# MegaShield.net
KiCad netlist of a schematic drawn in EAGLE
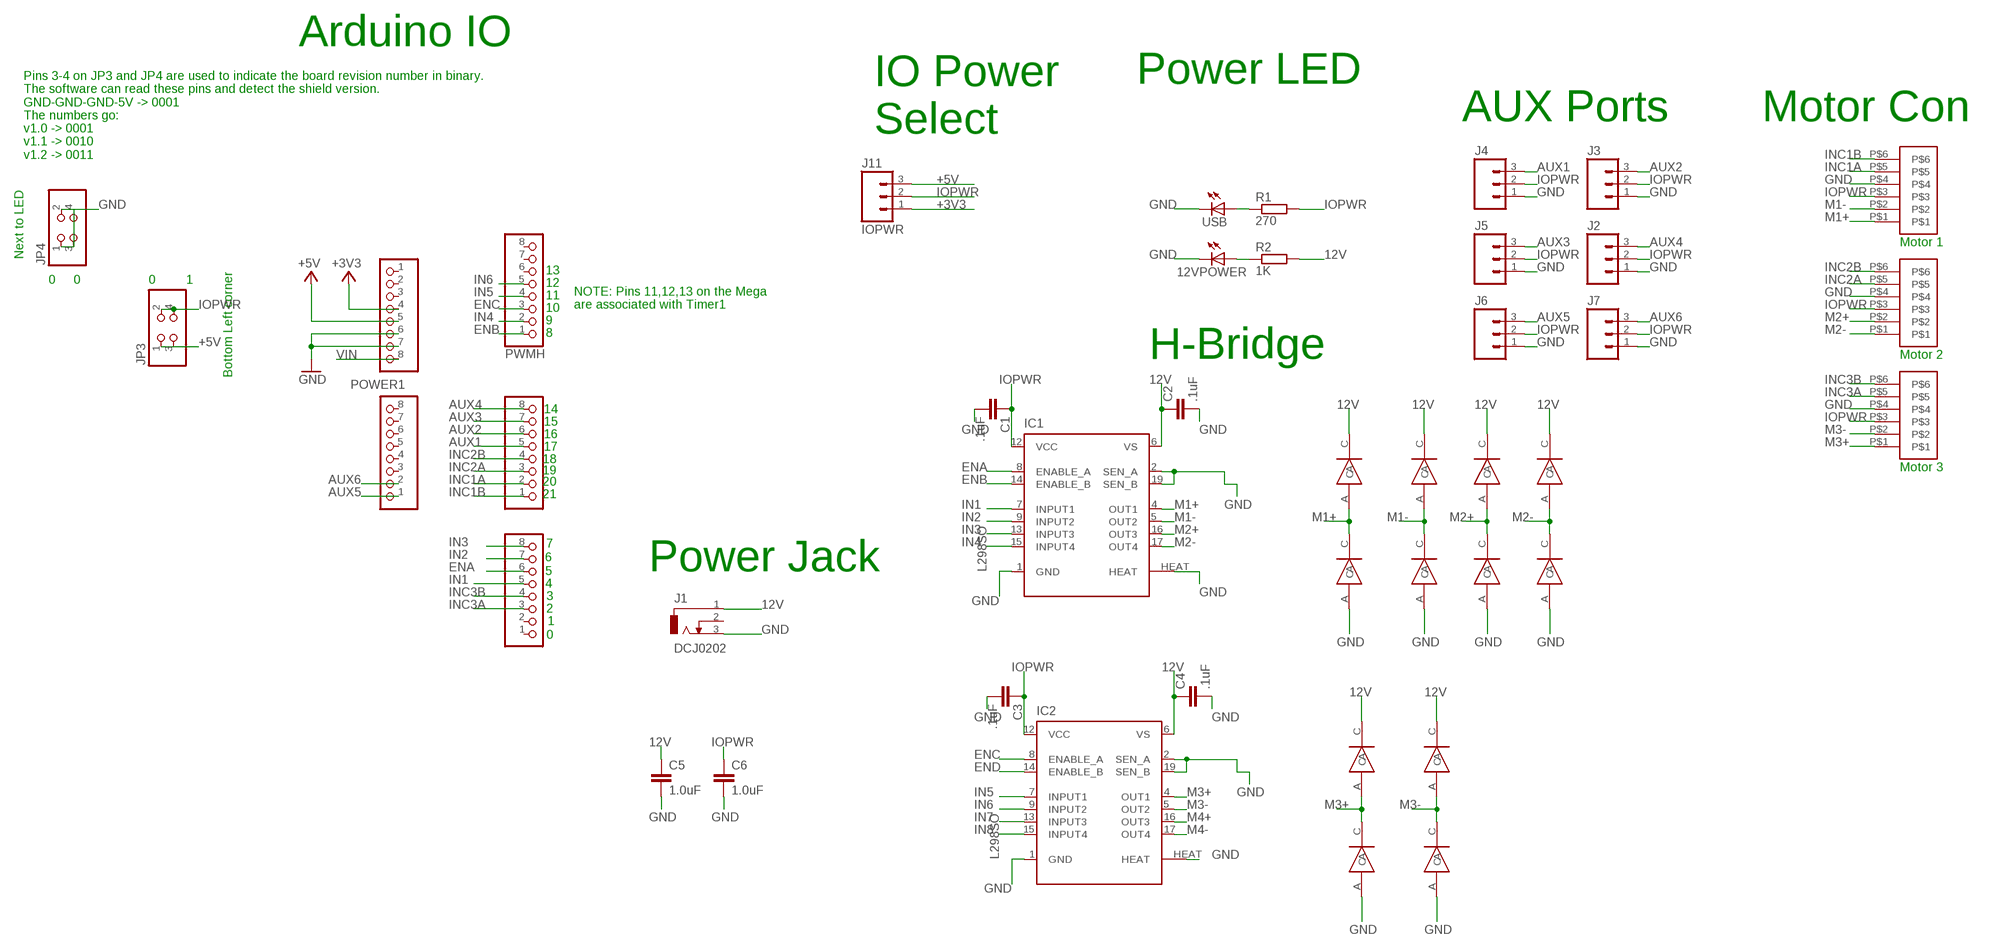
[diagram p0: schematic, sheet 1]

(export (version "E")
  (design (tool "Eeschema 10.0.6"))
  (components
    (comp (ref "12VPOWER")
      (value "LED_E")
      (footprint "eagle-import:LED_1206")
      (libsource (lib "eagle-import") (part "LED_E"))
    )
    (comp (ref "C1")
      (value ".1uF")
      (footprint "eagle-import:C0805")
      (libsource (lib "eagle-import") (part "C"))
    )
    (comp (ref "C2")
      (value ".1uF")
      (footprint "eagle-import:C0805")
      (libsource (lib "eagle-import") (part "C"))
    )
    (comp (ref "C3")
      (value ".1uF")
      (footprint "eagle-import:C0805")
      (libsource (lib "eagle-import") (part "C"))
    )
    (comp (ref "C4")
      (value ".1uF")
      (footprint "eagle-import:C0805")
      (libsource (lib "eagle-import") (part "C"))
    )
    (comp (ref "C5")
      (value "1.0uF")
      (footprint "eagle-import:0805-CAP")
      (libsource (lib "eagle-import") (part "1.0UF-25V-+80/-20(0805){dblquote}"))
    )
    (comp (ref "C6")
      (value "1.0uF")
      (footprint "eagle-import:0805-CAP")
      (libsource (lib "eagle-import") (part "1.0UF-25V-+80/-20(0805){dblquote}"))
    )
    (comp (ref "COMMUNICATION")
      (value "PINHD-1X8")
      (footprint "eagle-import:1X08")
      (libsource (lib "eagle-import") (part "pinhead_PINHD-1X8"))
    )
    (comp (ref "COMMUNICATION1")
      (value "PINHD-1X8")
      (footprint "eagle-import:1X08")
      (libsource (lib "eagle-import") (part "pinhead_PINHD-1X8"))
    )
    (comp (ref "IC1")
      (value "L298SO")
      (footprint "eagle-import:POWERSO-20")
      (libsource (lib "eagle-import") (part "L298SO"))
    )
    (comp (ref "IC2")
      (value "L298SO")
      (footprint "eagle-import:POWERSO-20")
      (libsource (lib "eagle-import") (part "L298SO"))
    )
    (comp (ref "J1")
      (value "DCJ0202")
      (footprint "eagle-import:DCJ0202")
      (libsource (lib "eagle-import") (part "DCJ0202"))
    )
    (comp (ref "J2")
      (value "M03LOCK")
      (footprint "eagle-import:1X03_LOCK")
      (libsource (lib "eagle-import") (part "M03LOCK"))
    )
    (comp (ref "J3")
      (value "M03LOCK")
      (footprint "eagle-import:1X03_LOCK")
      (libsource (lib "eagle-import") (part "M03LOCK"))
    )
    (comp (ref "J4")
      (value "M03LOCK")
      (footprint "eagle-import:1X03_LOCK")
      (libsource (lib "eagle-import") (part "M03LOCK"))
    )
    (comp (ref "J5")
      (value "M03LOCK")
      (footprint "eagle-import:1X03_LOCK")
      (libsource (lib "eagle-import") (part "M03LOCK"))
    )
    (comp (ref "J6")
      (value "M03LOCK")
      (footprint "eagle-import:1X03_LOCK")
      (libsource (lib "eagle-import") (part "M03LOCK"))
    )
    (comp (ref "J7")
      (value "M03LOCK")
      (footprint "eagle-import:1X03_LOCK")
      (libsource (lib "eagle-import") (part "M03LOCK"))
    )
    (comp (ref "J11")
      (value "IOPWR")
      (footprint "eagle-import:1X03_LOCK")
      (libsource (lib "eagle-import") (part "M03LOCK"))
    )
    (comp (ref "JP3")
      (value "PINHD-2X2")
      (footprint "eagle-import:2X02")
      (libsource (lib "eagle-import") (part "PINHD-2X2"))
    )
    (comp (ref "JP4")
      (value "PINHD-2X2")
      (footprint "eagle-import:2X02")
      (libsource (lib "eagle-import") (part "PINHD-2X2"))
    )
    (comp (ref "POWER1")
      (value "8x1F-H8.5")
      (footprint "eagle-import:1X08")
      (libsource (lib "eagle-import") (part "PINHD-1X8"))
    )
    (comp (ref "PWMH")
      (value "PINHD-1X8")
      (footprint "eagle-import:1X08")
      (libsource (lib "eagle-import") (part "pinhead_PINHD-1X8"))
    )
    (comp (ref "PWML")
      (value "PINHD-1X8")
      (footprint "eagle-import:1X08")
      (libsource (lib "eagle-import") (part "pinhead_PINHD-1X8"))
    )
    (comp (ref "R1")
      (value "270")
      (footprint "eagle-import:R0805")
      (libsource (lib "eagle-import") (part "R"))
    )
    (comp (ref "R2")
      (value "1K")
      (footprint "eagle-import:R0805")
      (libsource (lib "eagle-import") (part "R"))
    )
    (comp (ref "U$1")
      (value "JST-PH-6")
      (footprint "eagle-import:JST-PHR-6-SMD")
      (libsource (lib "eagle-import") (part "JST-PH-6"))
    )
    (comp (ref "U$2")
      (value "MRA4004")
      (footprint "eagle-import:SMA")
      (libsource (lib "eagle-import") (part "MRA4004"))
    )
    (comp (ref "U$3")
      (value "MRA4004")
      (footprint "eagle-import:SMA")
      (libsource (lib "eagle-import") (part "MRA4004"))
    )
    (comp (ref "U$4")
      (value "MRA4004")
      (footprint "eagle-import:SMA")
      (libsource (lib "eagle-import") (part "MRA4004"))
    )
    (comp (ref "U$5")
      (value "MRA4004")
      (footprint "eagle-import:SMA")
      (libsource (lib "eagle-import") (part "MRA4004"))
    )
    (comp (ref "U$6")
      (value "MRA4004")
      (footprint "eagle-import:SMA")
      (libsource (lib "eagle-import") (part "MRA4004"))
    )
    (comp (ref "U$7")
      (value "MRA4004")
      (footprint "eagle-import:SMA")
      (libsource (lib "eagle-import") (part "MRA4004"))
    )
    (comp (ref "U$8")
      (value "MRA4004")
      (footprint "eagle-import:SMA")
      (libsource (lib "eagle-import") (part "MRA4004"))
    )
    (comp (ref "U$9")
      (value "MRA4004")
      (footprint "eagle-import:SMA")
      (libsource (lib "eagle-import") (part "MRA4004"))
    )
    (comp (ref "U$10")
      (value "MRA4004")
      (footprint "eagle-import:SMA")
      (libsource (lib "eagle-import") (part "MRA4004"))
    )
    (comp (ref "U$11")
      (value "MRA4004")
      (footprint "eagle-import:SMA")
      (libsource (lib "eagle-import") (part "MRA4004"))
    )
    (comp (ref "U$12")
      (value "JST-PH-6")
      (footprint "eagle-import:JST-PHR-6-SMD")
      (libsource (lib "eagle-import") (part "JST-PH-6"))
    )
    (comp (ref "U$13")
      (value "MRA4004")
      (footprint "eagle-import:SMA")
      (libsource (lib "eagle-import") (part "MRA4004"))
    )
    (comp (ref "U$14")
      (value "MRA4004")
      (footprint "eagle-import:SMA")
      (libsource (lib "eagle-import") (part "MRA4004"))
    )
    (comp (ref "U$20")
      (value "JST-PH-6")
      (footprint "eagle-import:JST-PHR-6-SMD")
      (libsource (lib "eagle-import") (part "JST-PH-6"))
    )
    (comp (ref "USB")
      (value "LED_E")
      (footprint "eagle-import:LED_1206")
      (libsource (lib "eagle-import") (part "LED_E"))
    )
  )
  (nets
    (net (code "1") (name "+3V3") (class "Default")
      (node (ref "J11") (pin "1") (pinfunction "1_1") (pintype "passive"))
      (node (ref "POWER1") (pin "4") (pinfunction "4_4") (pintype "passive"))
    )
    (net (code "2") (name "+5V") (class "Default")
      (node (ref "J11") (pin "3") (pinfunction "3_3") (pintype "passive"))
      (node (ref "JP3") (pin "1") (pinfunction "1_1") (pintype "passive"))
      (node (ref "JP3") (pin "3") (pinfunction "3_3") (pintype "passive"))
      (node (ref "POWER1") (pin "5") (pinfunction "5_5") (pintype "passive"))
    )
    (net (code "3") (name "/12V") (class "Default")
      (node (ref "C2") (pin "1") (pinfunction "1_1") (pintype "passive"))
      (node (ref "C4") (pin "1") (pinfunction "1_1") (pintype "passive"))
      (node (ref "C5") (pin "1") (pinfunction "1_1") (pintype "passive"))
      (node (ref "IC1") (pin "6") (pinfunction "VS_6") (pintype "power_in"))
      (node (ref "IC2") (pin "6") (pinfunction "VS_6") (pintype "power_in"))
      (node (ref "J1") (pin "1") (pinfunction "1_1") (pintype "passive"))
      (node (ref "R2") (pin "2") (pinfunction "2_2") (pintype "passive"))
      (node (ref "U$13") (pin "C") (pinfunction "C_C") (pintype "bidirectional"))
      (node (ref "U$2") (pin "C") (pinfunction "C_C") (pintype "bidirectional"))
      (node (ref "U$3") (pin "C") (pinfunction "C_C") (pintype "bidirectional"))
      (node (ref "U$5") (pin "C") (pinfunction "C_C") (pintype "bidirectional"))
      (node (ref "U$7") (pin "C") (pinfunction "C_C") (pintype "bidirectional"))
      (node (ref "U$9") (pin "C") (pinfunction "C_C") (pintype "bidirectional"))
    )
    (net (code "4") (name "/AUX1") (class "Default")
      (node (ref "COMMUNICATION") (pin "5") (pinfunction "5_5") (pintype "passive"))
      (node (ref "J4") (pin "3") (pinfunction "3_3") (pintype "passive"))
    )
    (net (code "5") (name "/AUX2") (class "Default")
      (node (ref "COMMUNICATION") (pin "6") (pinfunction "6_6") (pintype "passive"))
      (node (ref "J3") (pin "3") (pinfunction "3_3") (pintype "passive"))
    )
    (net (code "6") (name "/AUX3") (class "Default")
      (node (ref "COMMUNICATION") (pin "7") (pinfunction "7_7") (pintype "passive"))
      (node (ref "J5") (pin "3") (pinfunction "3_3") (pintype "passive"))
    )
    (net (code "7") (name "/AUX4") (class "Default")
      (node (ref "COMMUNICATION") (pin "8") (pinfunction "8_8") (pintype "passive"))
      (node (ref "J2") (pin "3") (pinfunction "3_3") (pintype "passive"))
    )
    (net (code "8") (name "/AUX5") (class "Default")
      (node (ref "COMMUNICATION1") (pin "1") (pinfunction "1_1") (pintype "passive"))
      (node (ref "J6") (pin "3") (pinfunction "3_3") (pintype "passive"))
    )
    (net (code "9") (name "/AUX6") (class "Default")
      (node (ref "COMMUNICATION1") (pin "2") (pinfunction "2_2") (pintype "passive"))
      (node (ref "J7") (pin "3") (pinfunction "3_3") (pintype "passive"))
    )
    (net (code "10") (name "/ENA") (class "Default")
      (node (ref "IC1") (pin "8") (pinfunction "ENABLE_A_8") (pintype "input"))
      (node (ref "PWML") (pin "6") (pinfunction "6_6") (pintype "passive"))
    )
    (net (code "11") (name "/ENB") (class "Default")
      (node (ref "IC1") (pin "14") (pinfunction "ENABLE_B_14") (pintype "input"))
      (node (ref "PWMH") (pin "1") (pinfunction "1_1") (pintype "passive"))
    )
    (net (code "12") (name "/ENC") (class "Default")
      (node (ref "IC2") (pin "8") (pinfunction "ENABLE_A_8") (pintype "input"))
      (node (ref "PWMH") (pin "3") (pinfunction "3_3") (pintype "passive"))
    )
    (net (code "13") (name "/END") (class "Default")
      (node (ref "IC2") (pin "14") (pinfunction "ENABLE_B_14") (pintype "input"))
    )
    (net (code "14") (name "/IN1") (class "Default")
      (node (ref "IC1") (pin "7") (pinfunction "INPUT1_7") (pintype "input"))
      (node (ref "PWML") (pin "5") (pinfunction "5_5") (pintype "passive"))
    )
    (net (code "15") (name "/IN2") (class "Default")
      (node (ref "IC1") (pin "9") (pinfunction "INPUT2_9") (pintype "input"))
      (node (ref "PWML") (pin "7") (pinfunction "7_7") (pintype "passive"))
    )
    (net (code "16") (name "/IN3") (class "Default")
      (node (ref "IC1") (pin "13") (pinfunction "INPUT3_13") (pintype "input"))
      (node (ref "PWML") (pin "8") (pinfunction "8_8") (pintype "passive"))
    )
    (net (code "17") (name "/IN4") (class "Default")
      (node (ref "IC1") (pin "15") (pinfunction "INPUT4_15") (pintype "input"))
      (node (ref "PWMH") (pin "2") (pinfunction "2_2") (pintype "passive"))
    )
    (net (code "18") (name "/IN5") (class "Default")
      (node (ref "IC2") (pin "7") (pinfunction "INPUT1_7") (pintype "input"))
      (node (ref "PWMH") (pin "4") (pinfunction "4_4") (pintype "passive"))
    )
    (net (code "19") (name "/IN6") (class "Default")
      (node (ref "IC2") (pin "9") (pinfunction "INPUT2_9") (pintype "input"))
      (node (ref "PWMH") (pin "5") (pinfunction "5_5") (pintype "passive"))
    )
    (net (code "20") (name "/IN7") (class "Default")
      (node (ref "IC2") (pin "13") (pinfunction "INPUT3_13") (pintype "input"))
    )
    (net (code "21") (name "/IN8") (class "Default")
      (node (ref "IC2") (pin "15") (pinfunction "INPUT4_15") (pintype "input"))
    )
    (net (code "22") (name "/INC1A") (class "Default")
      (node (ref "COMMUNICATION") (pin "2") (pinfunction "2_2") (pintype "passive"))
      (node (ref "U$1") (pin "P$5") (pinfunction "P$5_P$5") (pintype "bidirectional"))
    )
    (net (code "23") (name "/INC1B") (class "Default")
      (node (ref "COMMUNICATION") (pin "1") (pinfunction "1_1") (pintype "passive"))
      (node (ref "U$1") (pin "P$6") (pinfunction "P$6_P$6") (pintype "bidirectional"))
    )
    (net (code "24") (name "/INC2A") (class "Default")
      (node (ref "COMMUNICATION") (pin "3") (pinfunction "3_3") (pintype "passive"))
      (node (ref "U$12") (pin "P$5") (pinfunction "P$5_P$5") (pintype "bidirectional"))
    )
    (net (code "25") (name "/INC2B") (class "Default")
      (node (ref "COMMUNICATION") (pin "4") (pinfunction "4_4") (pintype "passive"))
      (node (ref "U$12") (pin "P$6") (pinfunction "P$6_P$6") (pintype "bidirectional"))
    )
    (net (code "26") (name "/INC3A") (class "Default")
      (node (ref "PWML") (pin "3") (pinfunction "3_3") (pintype "passive"))
      (node (ref "U$20") (pin "P$5") (pinfunction "P$5_P$5") (pintype "bidirectional"))
    )
    (net (code "27") (name "/INC3B") (class "Default")
      (node (ref "PWML") (pin "4") (pinfunction "4_4") (pintype "passive"))
      (node (ref "U$20") (pin "P$6") (pinfunction "P$6_P$6") (pintype "bidirectional"))
    )
    (net (code "28") (name "/IOPWR") (class "Default")
      (node (ref "C1") (pin "1") (pinfunction "1_1") (pintype "passive"))
      (node (ref "C3") (pin "1") (pinfunction "1_1") (pintype "passive"))
      (node (ref "C6") (pin "1") (pinfunction "1_1") (pintype "passive"))
      (node (ref "IC1") (pin "12") (pinfunction "VCC_12") (pintype "power_in"))
      (node (ref "IC2") (pin "12") (pinfunction "VCC_12") (pintype "power_in"))
      (node (ref "J11") (pin "2") (pinfunction "2_2") (pintype "passive"))
      (node (ref "J2") (pin "2") (pinfunction "2_2") (pintype "passive"))
      (node (ref "J3") (pin "2") (pinfunction "2_2") (pintype "passive"))
      (node (ref "J4") (pin "2") (pinfunction "2_2") (pintype "passive"))
      (node (ref "J5") (pin "2") (pinfunction "2_2") (pintype "passive"))
      (node (ref "J6") (pin "2") (pinfunction "2_2") (pintype "passive"))
      (node (ref "J7") (pin "2") (pinfunction "2_2") (pintype "passive"))
      (node (ref "JP3") (pin "2") (pinfunction "2_2") (pintype "passive"))
      (node (ref "JP3") (pin "4") (pinfunction "4_4") (pintype "passive"))
      (node (ref "R1") (pin "2") (pinfunction "2_2") (pintype "passive"))
      (node (ref "U$1") (pin "P$3") (pinfunction "P$3_P$3") (pintype "bidirectional"))
      (node (ref "U$12") (pin "P$3") (pinfunction "P$3_P$3") (pintype "bidirectional"))
      (node (ref "U$20") (pin "P$3") (pinfunction "P$3_P$3") (pintype "bidirectional"))
    )
    (net (code "29") (name "/M1+") (class "Default")
      (node (ref "IC1") (pin "4") (pinfunction "OUT1_4") (pintype "output"))
      (node (ref "U$1") (pin "P$1") (pinfunction "P$1_P$1") (pintype "bidirectional"))
      (node (ref "U$3") (pin "A") (pinfunction "A_A") (pintype "bidirectional"))
      (node (ref "U$4") (pin "C") (pinfunction "C_C") (pintype "bidirectional"))
    )
    (net (code "30") (name "/M1-") (class "Default")
      (node (ref "IC1") (pin "5") (pinfunction "OUT2_5") (pintype "output"))
      (node (ref "U$1") (pin "P$2") (pinfunction "P$2_P$2") (pintype "bidirectional"))
      (node (ref "U$5") (pin "A") (pinfunction "A_A") (pintype "bidirectional"))
      (node (ref "U$6") (pin "C") (pinfunction "C_C") (pintype "bidirectional"))
    )
    (net (code "31") (name "/M2+") (class "Default")
      (node (ref "IC1") (pin "16") (pinfunction "OUT3_16") (pintype "output"))
      (node (ref "U$12") (pin "P$2") (pinfunction "P$2_P$2") (pintype "bidirectional"))
      (node (ref "U$7") (pin "A") (pinfunction "A_A") (pintype "bidirectional"))
      (node (ref "U$8") (pin "C") (pinfunction "C_C") (pintype "bidirectional"))
    )
    (net (code "32") (name "/M2-") (class "Default")
      (node (ref "IC1") (pin "17") (pinfunction "OUT4_17") (pintype "output"))
      (node (ref "U$10") (pin "C") (pinfunction "C_C") (pintype "bidirectional"))
      (node (ref "U$12") (pin "P$1") (pinfunction "P$1_P$1") (pintype "bidirectional"))
      (node (ref "U$9") (pin "A") (pinfunction "A_A") (pintype "bidirectional"))
    )
    (net (code "33") (name "/M3+") (class "Default")
      (node (ref "IC2") (pin "4") (pinfunction "OUT1_4") (pintype "output"))
      (node (ref "U$11") (pin "C") (pinfunction "C_C") (pintype "bidirectional"))
      (node (ref "U$2") (pin "A") (pinfunction "A_A") (pintype "bidirectional"))
      (node (ref "U$20") (pin "P$1") (pinfunction "P$1_P$1") (pintype "bidirectional"))
    )
    (net (code "34") (name "/M3-") (class "Default")
      (node (ref "IC2") (pin "5") (pinfunction "OUT2_5") (pintype "output"))
      (node (ref "U$13") (pin "A") (pinfunction "A_A") (pintype "bidirectional"))
      (node (ref "U$14") (pin "C") (pinfunction "C_C") (pintype "bidirectional"))
      (node (ref "U$20") (pin "P$2") (pinfunction "P$2_P$2") (pintype "bidirectional"))
    )
    (net (code "35") (name "/M4+") (class "Default")
      (node (ref "IC2") (pin "16") (pinfunction "OUT3_16") (pintype "output"))
    )
    (net (code "36") (name "/M4-") (class "Default")
      (node (ref "IC2") (pin "17") (pinfunction "OUT4_17") (pintype "output"))
    )
    (net (code "37") (name "/VIN") (class "Default")
      (node (ref "POWER1") (pin "8") (pinfunction "8_8") (pintype "passive"))
    )
    (net (code "38") (name "GND") (class "Default")
      (node (ref "12VPOWER") (pin "C") (pinfunction "C_C") (pintype "passive"))
      (node (ref "C1") (pin "2") (pinfunction "2_2") (pintype "passive"))
      (node (ref "C2") (pin "2") (pinfunction "2_2") (pintype "passive"))
      (node (ref "C3") (pin "2") (pinfunction "2_2") (pintype "passive"))
      (node (ref "C4") (pin "2") (pinfunction "2_2") (pintype "passive"))
      (node (ref "C5") (pin "2") (pinfunction "2_2") (pintype "passive"))
      (node (ref "C6") (pin "2") (pinfunction "2_2") (pintype "passive"))
      (node (ref "IC1") (pin "1") (pinfunction "GND_1") (pintype "power_in"))
      (node (ref "IC1") (pin "19") (pinfunction "SEN_B_19") (pintype "input"))
      (node (ref "IC1") (pin "2") (pinfunction "SEN_A_2") (pintype "input"))
      (node (ref "IC1") (pin "HEAT") (pinfunction "HEAT_HEAT") (pintype "bidirectional"))
      (node (ref "IC2") (pin "1") (pinfunction "GND_1") (pintype "power_in"))
      (node (ref "IC2") (pin "19") (pinfunction "SEN_B_19") (pintype "input"))
      (node (ref "IC2") (pin "2") (pinfunction "SEN_A_2") (pintype "input"))
      (node (ref "IC2") (pin "HEAT") (pinfunction "HEAT_HEAT") (pintype "bidirectional"))
      (node (ref "J1") (pin "3") (pinfunction "3_3") (pintype "passive"))
      (node (ref "J2") (pin "1") (pinfunction "1_1") (pintype "passive"))
      (node (ref "J3") (pin "1") (pinfunction "1_1") (pintype "passive"))
      (node (ref "J4") (pin "1") (pinfunction "1_1") (pintype "passive"))
      (node (ref "J5") (pin "1") (pinfunction "1_1") (pintype "passive"))
      (node (ref "J6") (pin "1") (pinfunction "1_1") (pintype "passive"))
      (node (ref "J7") (pin "1") (pinfunction "1_1") (pintype "passive"))
      (node (ref "JP4") (pin "1") (pinfunction "1_1") (pintype "passive"))
      (node (ref "JP4") (pin "2") (pinfunction "2_2") (pintype "passive"))
      (node (ref "JP4") (pin "3") (pinfunction "3_3") (pintype "passive"))
      (node (ref "JP4") (pin "4") (pinfunction "4_4") (pintype "passive"))
      (node (ref "POWER1") (pin "6") (pinfunction "6_6") (pintype "passive"))
      (node (ref "POWER1") (pin "7") (pinfunction "7_7") (pintype "passive"))
      (node (ref "U$1") (pin "P$4") (pinfunction "P$4_P$4") (pintype "bidirectional"))
      (node (ref "U$10") (pin "A") (pinfunction "A_A") (pintype "bidirectional"))
      (node (ref "U$11") (pin "A") (pinfunction "A_A") (pintype "bidirectional"))
      (node (ref "U$12") (pin "P$4") (pinfunction "P$4_P$4") (pintype "bidirectional"))
      (node (ref "U$14") (pin "A") (pinfunction "A_A") (pintype "bidirectional"))
      (node (ref "U$20") (pin "P$4") (pinfunction "P$4_P$4") (pintype "bidirectional"))
      (node (ref "U$4") (pin "A") (pinfunction "A_A") (pintype "bidirectional"))
      (node (ref "U$6") (pin "A") (pinfunction "A_A") (pintype "bidirectional"))
      (node (ref "U$8") (pin "A") (pinfunction "A_A") (pintype "bidirectional"))
      (node (ref "USB") (pin "C") (pinfunction "C_C") (pintype "passive"))
    )
    (net (code "39") (name "Net-(12VPOWER-PadA)") (class "Default")
      (node (ref "12VPOWER") (pin "A") (pinfunction "A_A") (pintype "passive"))
      (node (ref "R2") (pin "1") (pinfunction "1_1") (pintype "passive"))
    )
    (net (code "40") (name "Net-(R1-Pad1)") (class "Default")
      (node (ref "R1") (pin "1") (pinfunction "1_1") (pintype "passive"))
      (node (ref "USB") (pin "A") (pinfunction "A_A") (pintype "passive"))
    )
    (net (code "41") (name "unconnected-(COMMUNICATION1-Pad3)") (class "Default")
      (node (ref "COMMUNICATION1") (pin "3") (pinfunction "3_3") (pintype "passive"))
    )
    (net (code "42") (name "unconnected-(COMMUNICATION1-Pad4)") (class "Default")
      (node (ref "COMMUNICATION1") (pin "4") (pinfunction "4_4") (pintype "passive"))
    )
    (net (code "43") (name "unconnected-(COMMUNICATION1-Pad5)") (class "Default")
      (node (ref "COMMUNICATION1") (pin "5") (pinfunction "5_5") (pintype "passive"))
    )
    (net (code "44") (name "unconnected-(COMMUNICATION1-Pad6)") (class "Default")
      (node (ref "COMMUNICATION1") (pin "6") (pinfunction "6_6") (pintype "passive"))
    )
    (net (code "45") (name "unconnected-(COMMUNICATION1-Pad7)") (class "Default")
      (node (ref "COMMUNICATION1") (pin "7") (pinfunction "7_7") (pintype "passive"))
    )
    (net (code "46") (name "unconnected-(COMMUNICATION1-Pad8)") (class "Default")
      (node (ref "COMMUNICATION1") (pin "8") (pinfunction "8_8") (pintype "passive"))
    )
    (net (code "47") (name "unconnected-(J1-Pad2)") (class "Default")
      (node (ref "J1") (pin "2") (pinfunction "2_2") (pintype "passive"))
    )
    (net (code "48") (name "unconnected-(POWER1-Pad1)") (class "Default")
      (node (ref "POWER1") (pin "1") (pinfunction "1_1") (pintype "passive"))
    )
    (net (code "49") (name "unconnected-(POWER1-Pad2)") (class "Default")
      (node (ref "POWER1") (pin "2") (pinfunction "2_2") (pintype "passive"))
    )
    (net (code "50") (name "unconnected-(POWER1-Pad3)") (class "Default")
      (node (ref "POWER1") (pin "3") (pinfunction "3_3") (pintype "passive"))
    )
    (net (code "51") (name "unconnected-(PWMH-Pad6)") (class "Default")
      (node (ref "PWMH") (pin "6") (pinfunction "6_6") (pintype "passive"))
    )
    (net (code "52") (name "unconnected-(PWMH-Pad7)") (class "Default")
      (node (ref "PWMH") (pin "7") (pinfunction "7_7") (pintype "passive"))
    )
    (net (code "53") (name "unconnected-(PWMH-Pad8)") (class "Default")
      (node (ref "PWMH") (pin "8") (pinfunction "8_8") (pintype "passive"))
    )
    (net (code "54") (name "unconnected-(PWML-Pad1)") (class "Default")
      (node (ref "PWML") (pin "1") (pinfunction "1_1") (pintype "passive"))
    )
    (net (code "55") (name "unconnected-(PWML-Pad2)") (class "Default")
      (node (ref "PWML") (pin "2") (pinfunction "2_2") (pintype "passive"))
    )
  )
)
